# tm7_LEDs.net
KiCad netlist of a schematic drawn in EAGLE
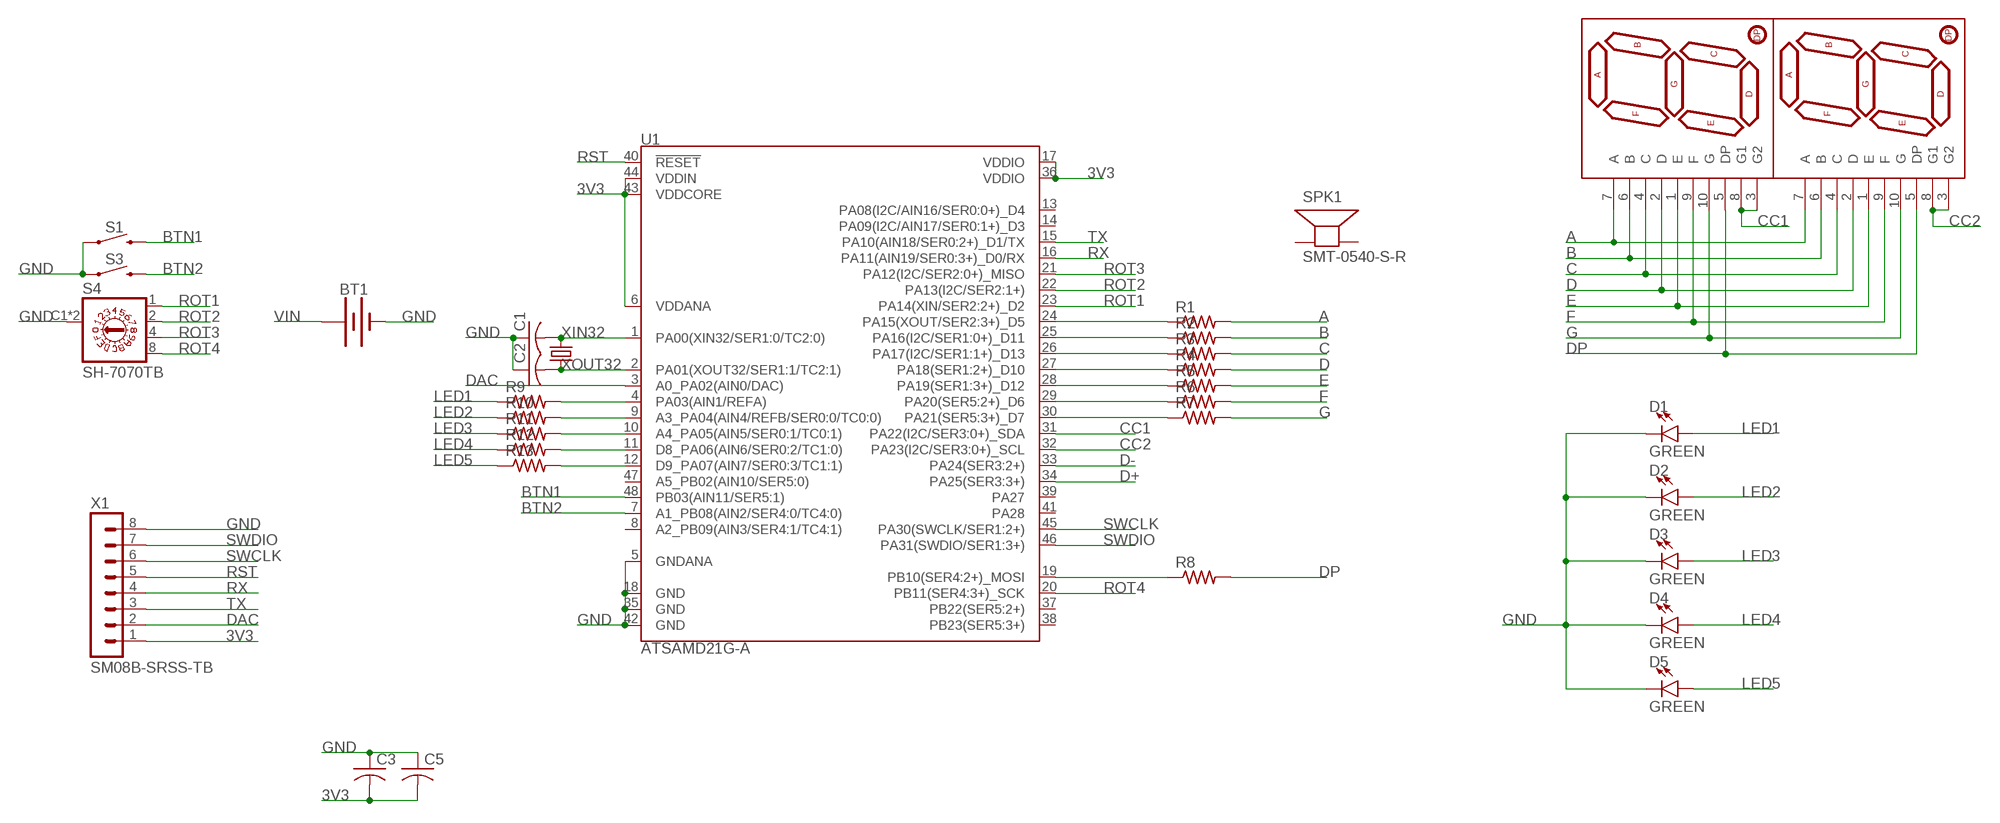
[diagram p0: schematic, sheet 1]

(export (version "E")
  (design (tool "Eeschema 10.0.6"))
  (components
    (comp (ref "BT1")
      (value "BATTERY-20MM_SMD_4LEGS_OVERPASTE_INNER")
      (footprint "eagle-import:BATTCON_20MM_4LEGS_OVERPASTE_INNER")
      (libsource (lib "eagle-import") (part "BATTERY-20MM_SMD_4LEGS_OVERPASTE_INNER"))
    )
    (comp (ref "C1")
      (value "C-USC0603")
      (footprint "eagle-import:C0603")
      (libsource (lib "eagle-import") (part "C-USC0603"))
    )
    (comp (ref "C2")
      (value "C-USC0603")
      (footprint "eagle-import:C0603")
      (libsource (lib "eagle-import") (part "C-USC0603"))
    )
    (comp (ref "C3")
      (value "C-USC0603")
      (footprint "eagle-import:C0603")
      (libsource (lib "eagle-import") (part "C-USC0603"))
    )
    (comp (ref "C5")
      (value "C-USC0603")
      (footprint "eagle-import:C0603")
      (libsource (lib "eagle-import") (part "C-USC0603"))
    )
    (comp (ref "D1")
      (value "GREEN")
      (footprint "eagle-import:LED-1206")
      (libsource (lib "eagle-import") (part "LED-GREEN1206"))
    )
    (comp (ref "D2")
      (value "GREEN")
      (footprint "eagle-import:LED-1206")
      (libsource (lib "eagle-import") (part "LED-GREEN1206"))
    )
    (comp (ref "D3")
      (value "GREEN")
      (footprint "eagle-import:LED-1206")
      (libsource (lib "eagle-import") (part "LED-GREEN1206"))
    )
    (comp (ref "D4")
      (value "GREEN")
      (footprint "eagle-import:LED-1206")
      (libsource (lib "eagle-import") (part "LED-GREEN1206"))
    )
    (comp (ref "D5")
      (value "GREEN")
      (footprint "eagle-import:LED-1206")
      (libsource (lib "eagle-import") (part "LED-GREEN1206"))
    )
    (comp (ref "R1")
      (value "R-US_R0603")
      (footprint "eagle-import:R0603")
      (libsource (lib "eagle-import") (part "R-US_R0603"))
    )
    (comp (ref "R2")
      (value "R-US_R0603")
      (footprint "eagle-import:R0603")
      (libsource (lib "eagle-import") (part "R-US_R0603"))
    )
    (comp (ref "R3")
      (value "R-US_R0603")
      (footprint "eagle-import:R0603")
      (libsource (lib "eagle-import") (part "R-US_R0603"))
    )
    (comp (ref "R4")
      (value "R-US_R0603")
      (footprint "eagle-import:R0603")
      (libsource (lib "eagle-import") (part "R-US_R0603"))
    )
    (comp (ref "R5")
      (value "R-US_R0603")
      (footprint "eagle-import:R0603")
      (libsource (lib "eagle-import") (part "R-US_R0603"))
    )
    (comp (ref "R6")
      (value "R-US_R0603")
      (footprint "eagle-import:R0603")
      (libsource (lib "eagle-import") (part "R-US_R0603"))
    )
    (comp (ref "R7")
      (value "R-US_R0603")
      (footprint "eagle-import:R0603")
      (libsource (lib "eagle-import") (part "R-US_R0603"))
    )
    (comp (ref "R8")
      (value "R-US_R0603")
      (footprint "eagle-import:R0603")
      (libsource (lib "eagle-import") (part "R-US_R0603"))
    )
    (comp (ref "R9")
      (value "R-US_R0603")
      (footprint "eagle-import:R0603")
      (libsource (lib "eagle-import") (part "R-US_R0603"))
    )
    (comp (ref "R10")
      (value "R-US_R0603")
      (footprint "eagle-import:R0603")
      (libsource (lib "eagle-import") (part "R-US_R0603"))
    )
    (comp (ref "R11")
      (value "R-US_R0603")
      (footprint "eagle-import:R0603")
      (libsource (lib "eagle-import") (part "R-US_R0603"))
    )
    (comp (ref "R12")
      (value "R-US_R0603")
      (footprint "eagle-import:R0603")
      (libsource (lib "eagle-import") (part "R-US_R0603"))
    )
    (comp (ref "R13")
      (value "R-US_R0603")
      (footprint "eagle-import:R0603")
      (libsource (lib "eagle-import") (part "R-US_R0603"))
    )
    (comp (ref "S1")
      (value "MOMENTARY-SWITCH-SPST-SMD-6.2MM-TALL")
      (footprint "eagle-import:TACTILE_SWITCH_SMD_6.2MM_TALL")
      (libsource (lib "eagle-import") (part "MOMENTARY-SWITCH-SPST-SMD-6.2MM-TALL"))
    )
    (comp (ref "S3")
      (value "MOMENTARY-SWITCH-SPST-SMD-6.2MM-TALL")
      (footprint "eagle-import:TACTILE_SWITCH_SMD_6.2MM_TALL")
      (libsource (lib "eagle-import") (part "MOMENTARY-SWITCH-SPST-SMD-6.2MM-TALL"))
    )
    (comp (ref "S4")
      (value "SH-7070TB")
      (footprint "eagle-import:SH-7070B")
      (fields (field (name "MF") "Nidec Copal"))
      (libsource (lib "eagle-import") (part "SH-7070TB"))
    )
    (comp (ref "SPK1")
      (value "SMT-0540-S-R")
      (footprint "eagle-import:SMT-0540-S-R")
      (fields (field (name "MF") "PUI"))
      (libsource (lib "eagle-import") (part "SMT-0540-S-R"))
    )
    (comp (ref "U$2")
      (value "7-SEGMENT-DISPLAY-1\"-RED")
      (footprint "eagle-import:7-SEGMENT-SMD")
      (libsource (lib "eagle-import") (part "7-SEGMENT-DISPLAY-1{dblquote}-RED"))
    )
    (comp (ref "U$3")
      (value "7-SEGMENT-DISPLAY-1\"-RED")
      (footprint "eagle-import:7-SEGMENT-SMD")
      (libsource (lib "eagle-import") (part "7-SEGMENT-DISPLAY-1{dblquote}-RED"))
    )
    (comp (ref "U1")
      (value "ATSAMD21G-A")
      (footprint "eagle-import:TQFP-48")
      (libsource (lib "eagle-import") (part "ATSAMD21G-A"))
    )
    (comp (ref "X1")
      (value "SM08B-SRSS-TB")
      (footprint "eagle-import:SM08B-SRSS-TB")
      (libsource (lib "eagle-import") (part "SM08B-SRSS-TB"))
    )
    (comp (ref "Y1")
      (value "32.768kHz")
      (footprint "eagle-import:CRYSTAL-SMD-3.2X1.5MM")
      (libsource (lib "eagle-import") (part "CRYSTAL-32.768KHZSMD-3.2X1.5"))
    )
  )
  (nets
    (net (code "1") (name "/3V3") (class "Default")
      (node (ref "C3") (pin "2") (pinfunction "2_2") (pintype "passive"))
      (node (ref "C5") (pin "2") (pinfunction "2_2") (pintype "passive"))
      (node (ref "U1") (pin "17") (pinfunction "VDDIO_17") (pintype "bidirectional"))
      (node (ref "U1") (pin "36") (pinfunction "VDDIO_36") (pintype "bidirectional"))
      (node (ref "U1") (pin "43") (pinfunction "VDDCORE_43") (pintype "bidirectional"))
      (node (ref "U1") (pin "44") (pinfunction "VDDIN_44") (pintype "bidirectional"))
      (node (ref "U1") (pin "6") (pinfunction "VDDANA_6") (pintype "bidirectional"))
      (node (ref "X1") (pin "1") (pinfunction "1_1") (pintype "passive"))
    )
    (net (code "2") (name "/A") (class "Default")
      (node (ref "R1") (pin "2") (pinfunction "2_2") (pintype "passive"))
      (node (ref "U$2") (pin "7") (pinfunction "A_7") (pintype "bidirectional"))
      (node (ref "U$3") (pin "7") (pinfunction "A_7") (pintype "bidirectional"))
    )
    (net (code "3") (name "/B") (class "Default")
      (node (ref "R2") (pin "2") (pinfunction "2_2") (pintype "passive"))
      (node (ref "U$2") (pin "6") (pinfunction "B_6") (pintype "bidirectional"))
      (node (ref "U$3") (pin "6") (pinfunction "B_6") (pintype "bidirectional"))
    )
    (net (code "4") (name "/BTN1") (class "Default")
      (node (ref "S1") (pin "B2") (pinfunction "2_B2") (pintype "passive"))
      (node (ref "U1") (pin "48") (pinfunction "PB03(AIN11/SER5:1)_48") (pintype "bidirectional"))
    )
    (net (code "5") (name "/BTN2") (class "Default")
      (node (ref "S3") (pin "B2") (pinfunction "2_B2") (pintype "passive"))
      (node (ref "U1") (pin "7") (pinfunction "A1_PB08(AIN2/SER4:0/TC4:0)_7") (pintype "bidirectional"))
    )
    (net (code "6") (name "/C") (class "Default")
      (node (ref "R3") (pin "2") (pinfunction "2_2") (pintype "passive"))
      (node (ref "U$2") (pin "4") (pinfunction "C_4") (pintype "bidirectional"))
      (node (ref "U$3") (pin "4") (pinfunction "C_4") (pintype "bidirectional"))
    )
    (net (code "7") (name "/CC1") (class "Default")
      (node (ref "U$2") (pin "3") (pinfunction "G2_3") (pintype "bidirectional"))
      (node (ref "U$2") (pin "8") (pinfunction "G1_8") (pintype "bidirectional"))
      (node (ref "U1") (pin "31") (pinfunction "PA22(I2C/SER3:0+)_SDA_31") (pintype "bidirectional"))
    )
    (net (code "8") (name "/CC2") (class "Default")
      (node (ref "U$3") (pin "3") (pinfunction "G2_3") (pintype "bidirectional"))
      (node (ref "U$3") (pin "8") (pinfunction "G1_8") (pintype "bidirectional"))
      (node (ref "U1") (pin "32") (pinfunction "PA23(I2C/SER3:0+)_SCL_32") (pintype "bidirectional"))
    )
    (net (code "9") (name "/D") (class "Default")
      (node (ref "R4") (pin "2") (pinfunction "2_2") (pintype "passive"))
      (node (ref "U$2") (pin "2") (pinfunction "D_2") (pintype "bidirectional"))
      (node (ref "U$3") (pin "2") (pinfunction "D_2") (pintype "bidirectional"))
    )
    (net (code "10") (name "/D+") (class "Default")
      (node (ref "U1") (pin "34") (pinfunction "PA25(SER3:3+)_34") (pintype "bidirectional"))
    )
    (net (code "11") (name "/D-") (class "Default")
      (node (ref "U1") (pin "33") (pinfunction "PA24(SER3:2+)_33") (pintype "bidirectional"))
    )
    (net (code "12") (name "/DAC") (class "Default")
      (node (ref "U1") (pin "3") (pinfunction "A0_PA02(AIN0/DAC)_3") (pintype "bidirectional"))
      (node (ref "X1") (pin "2") (pinfunction "2_2") (pintype "passive"))
    )
    (net (code "13") (name "/DP") (class "Default")
      (node (ref "R8") (pin "2") (pinfunction "2_2") (pintype "passive"))
      (node (ref "U$2") (pin "5") (pinfunction "DP_5") (pintype "bidirectional"))
      (node (ref "U$3") (pin "5") (pinfunction "DP_5") (pintype "bidirectional"))
    )
    (net (code "14") (name "/E") (class "Default")
      (node (ref "R5") (pin "2") (pinfunction "2_2") (pintype "passive"))
      (node (ref "U$2") (pin "1") (pinfunction "E_1") (pintype "bidirectional"))
      (node (ref "U$3") (pin "1") (pinfunction "E_1") (pintype "bidirectional"))
    )
    (net (code "15") (name "/F") (class "Default")
      (node (ref "R6") (pin "2") (pinfunction "2_2") (pintype "passive"))
      (node (ref "U$2") (pin "9") (pinfunction "F_9") (pintype "bidirectional"))
      (node (ref "U$3") (pin "9") (pinfunction "F_9") (pintype "bidirectional"))
    )
    (net (code "16") (name "/G") (class "Default")
      (node (ref "R7") (pin "2") (pinfunction "2_2") (pintype "passive"))
      (node (ref "U$2") (pin "10") (pinfunction "G_10") (pintype "bidirectional"))
      (node (ref "U$3") (pin "10") (pinfunction "G_10") (pintype "bidirectional"))
    )
    (net (code "17") (name "/GND") (class "Default")
      (node (ref "BT1") (pin "2") (pinfunction "-_2") (pintype "power_in"))
      (node (ref "C1") (pin "1") (pinfunction "1_1") (pintype "passive"))
      (node (ref "C2") (pin "1") (pinfunction "1_1") (pintype "passive"))
      (node (ref "C3") (pin "1") (pinfunction "1_1") (pintype "passive"))
      (node (ref "C5") (pin "1") (pinfunction "1_1") (pintype "passive"))
      (node (ref "D1") (pin "C") (pinfunction "C_C") (pintype "passive"))
      (node (ref "D2") (pin "C") (pinfunction "C_C") (pintype "passive"))
      (node (ref "D3") (pin "C") (pinfunction "C_C") (pintype "passive"))
      (node (ref "D4") (pin "C") (pinfunction "C_C") (pintype "passive"))
      (node (ref "D5") (pin "C") (pinfunction "C_C") (pintype "passive"))
      (node (ref "S1") (pin "A2") (pinfunction "1_A2") (pintype "passive"))
      (node (ref "S3") (pin "A2") (pinfunction "1_A2") (pintype "passive"))
      (node (ref "S4") (pin "C1") (pinfunction "C_C1") (pintype "passive"))
      (node (ref "S4") (pin "C2") (pinfunction "C_C2") (pintype "passive"))
      (node (ref "U1") (pin "18") (pinfunction "GND_18") (pintype "bidirectional"))
      (node (ref "U1") (pin "35") (pinfunction "GND_35") (pintype "bidirectional"))
      (node (ref "U1") (pin "42") (pinfunction "GND_42") (pintype "bidirectional"))
      (node (ref "U1") (pin "5") (pinfunction "GNDANA_5") (pintype "bidirectional"))
      (node (ref "X1") (pin "8") (pinfunction "8_8") (pintype "passive"))
    )
    (net (code "18") (name "/LED1") (class "Default")
      (node (ref "D1") (pin "A") (pinfunction "A_A") (pintype "passive"))
      (node (ref "R9") (pin "1") (pinfunction "1_1") (pintype "passive"))
    )
    (net (code "19") (name "/LED2") (class "Default")
      (node (ref "D2") (pin "A") (pinfunction "A_A") (pintype "passive"))
      (node (ref "R10") (pin "1") (pinfunction "1_1") (pintype "passive"))
    )
    (net (code "20") (name "/LED3") (class "Default")
      (node (ref "D3") (pin "A") (pinfunction "A_A") (pintype "passive"))
      (node (ref "R11") (pin "1") (pinfunction "1_1") (pintype "passive"))
    )
    (net (code "21") (name "/LED4") (class "Default")
      (node (ref "D4") (pin "A") (pinfunction "A_A") (pintype "passive"))
      (node (ref "R12") (pin "1") (pinfunction "1_1") (pintype "passive"))
    )
    (net (code "22") (name "/LED5") (class "Default")
      (node (ref "D5") (pin "A") (pinfunction "A_A") (pintype "passive"))
      (node (ref "R13") (pin "1") (pinfunction "1_1") (pintype "passive"))
    )
    (net (code "23") (name "/ROT1") (class "Default")
      (node (ref "S4") (pin "1") (pinfunction "1_1") (pintype "passive"))
      (node (ref "U1") (pin "23") (pinfunction "PA14(XIN/SER2:2+)_D2_23") (pintype "bidirectional"))
    )
    (net (code "24") (name "/ROT2") (class "Default")
      (node (ref "S4") (pin "2") (pinfunction "2_2") (pintype "passive"))
      (node (ref "U1") (pin "22") (pinfunction "PA13(I2C/SER2:1+)_22") (pintype "bidirectional"))
    )
    (net (code "25") (name "/ROT3") (class "Default")
      (node (ref "S4") (pin "4") (pinfunction "4_4") (pintype "passive"))
      (node (ref "U1") (pin "21") (pinfunction "PA12(I2C/SER2:0+)_MISO_21") (pintype "bidirectional"))
    )
    (net (code "26") (name "/ROT4") (class "Default")
      (node (ref "S4") (pin "8") (pinfunction "8_8") (pintype "passive"))
      (node (ref "U1") (pin "20") (pinfunction "PB11(SER4:3+)_SCK_20") (pintype "bidirectional"))
    )
    (net (code "27") (name "/RST") (class "Default")
      (node (ref "U1") (pin "40") (pinfunction "~{RESET}_40") (pintype "bidirectional"))
      (node (ref "X1") (pin "5") (pinfunction "5_5") (pintype "passive"))
    )
    (net (code "28") (name "/RX") (class "Default")
      (node (ref "U1") (pin "16") (pinfunction "PA11(AIN19/SER0:3+)_D0/RX_16") (pintype "bidirectional"))
      (node (ref "X1") (pin "4") (pinfunction "4_4") (pintype "passive"))
    )
    (net (code "29") (name "/SWCLK") (class "Default")
      (node (ref "U1") (pin "45") (pinfunction "PA30(SWCLK/SER1:2+)_45") (pintype "bidirectional"))
      (node (ref "X1") (pin "6") (pinfunction "6_6") (pintype "passive"))
    )
    (net (code "30") (name "/SWDIO") (class "Default")
      (node (ref "U1") (pin "46") (pinfunction "PA31(SWDIO/SER1:3+)_46") (pintype "bidirectional"))
      (node (ref "X1") (pin "7") (pinfunction "7_7") (pintype "passive"))
    )
    (net (code "31") (name "/TX") (class "Default")
      (node (ref "U1") (pin "15") (pinfunction "PA10(AIN18/SER0:2+)_D1/TX_15") (pintype "bidirectional"))
      (node (ref "X1") (pin "3") (pinfunction "3_3") (pintype "passive"))
    )
    (net (code "32") (name "/VIN") (class "Default")
      (node (ref "BT1") (pin "1") (pinfunction "+_1") (pintype "power_in"))
    )
    (net (code "33") (name "/XIN32") (class "Default")
      (node (ref "C1") (pin "2") (pinfunction "2_2") (pintype "passive"))
      (node (ref "U1") (pin "1") (pinfunction "PA00(XIN32/SER1:0/TC2:0)_1") (pintype "bidirectional"))
      (node (ref "Y1") (pin "P$2") (pinfunction "2_P$2") (pintype "passive"))
    )
    (net (code "34") (name "/XOUT32") (class "Default")
      (node (ref "C2") (pin "2") (pinfunction "2_2") (pintype "passive"))
      (node (ref "U1") (pin "2") (pinfunction "PA01(XOUT32/SER1:1/TC2:1)_2") (pintype "bidirectional"))
      (node (ref "Y1") (pin "P$1") (pinfunction "1_P$1") (pintype "passive"))
    )
    (net (code "35") (name "Net-(U1-A3_PA04(AIN4{slash}REFB{slash}SER0:0{slash}TC0:0))") (class "Default")
      (node (ref "R10") (pin "2") (pinfunction "2_2") (pintype "passive"))
      (node (ref "U1") (pin "9") (pinfunction "A3_PA04(AIN4/REFB/SER0:0/TC0:0)_9") (pintype "bidirectional"))
    )
    (net (code "36") (name "Net-(U1-A4_PA05(AIN5{slash}SER0:1{slash}TC0:1))") (class "Default")
      (node (ref "R11") (pin "2") (pinfunction "2_2") (pintype "passive"))
      (node (ref "U1") (pin "10") (pinfunction "A4_PA05(AIN5/SER0:1/TC0:1)_10") (pintype "bidirectional"))
    )
    (net (code "37") (name "Net-(U1-D8_PA06(AIN6{slash}SER0:2{slash}TC1:0))") (class "Default")
      (node (ref "R12") (pin "2") (pinfunction "2_2") (pintype "passive"))
      (node (ref "U1") (pin "11") (pinfunction "D8_PA06(AIN6/SER0:2/TC1:0)_11") (pintype "bidirectional"))
    )
    (net (code "38") (name "Net-(U1-D9_PA07(AIN7{slash}SER0:3{slash}TC1:1))") (class "Default")
      (node (ref "R13") (pin "2") (pinfunction "2_2") (pintype "passive"))
      (node (ref "U1") (pin "12") (pinfunction "D9_PA07(AIN7/SER0:3/TC1:1)_12") (pintype "bidirectional"))
    )
    (net (code "39") (name "Net-(U1-PA03(AIN1{slash}REFA))") (class "Default")
      (node (ref "R9") (pin "2") (pinfunction "2_2") (pintype "passive"))
      (node (ref "U1") (pin "4") (pinfunction "PA03(AIN1/REFA)_4") (pintype "bidirectional"))
    )
    (net (code "40") (name "Net-(U1-PA15(XOUT{slash}SER2:3+)_D5)") (class "Default")
      (node (ref "R1") (pin "1") (pinfunction "1_1") (pintype "passive"))
      (node (ref "U1") (pin "24") (pinfunction "PA15(XOUT/SER2:3+)_D5_24") (pintype "bidirectional"))
    )
    (net (code "41") (name "Net-(U1-PA16(I2C{slash}SER1:0+)_D11)") (class "Default")
      (node (ref "R2") (pin "1") (pinfunction "1_1") (pintype "passive"))
      (node (ref "U1") (pin "25") (pinfunction "PA16(I2C/SER1:0+)_D11_25") (pintype "bidirectional"))
    )
    (net (code "42") (name "Net-(U1-PA17(I2C{slash}SER1:1+)_D13)") (class "Default")
      (node (ref "R3") (pin "1") (pinfunction "1_1") (pintype "passive"))
      (node (ref "U1") (pin "26") (pinfunction "PA17(I2C/SER1:1+)_D13_26") (pintype "bidirectional"))
    )
    (net (code "43") (name "Net-(U1-PA18(SER1:2+)_D10)") (class "Default")
      (node (ref "R4") (pin "1") (pinfunction "1_1") (pintype "passive"))
      (node (ref "U1") (pin "27") (pinfunction "PA18(SER1:2+)_D10_27") (pintype "bidirectional"))
    )
    (net (code "44") (name "Net-(U1-PA19(SER1:3+)_D12)") (class "Default")
      (node (ref "R5") (pin "1") (pinfunction "1_1") (pintype "passive"))
      (node (ref "U1") (pin "28") (pinfunction "PA19(SER1:3+)_D12_28") (pintype "bidirectional"))
    )
    (net (code "45") (name "Net-(U1-PA20(SER5:2+)_D6)") (class "Default")
      (node (ref "R6") (pin "1") (pinfunction "1_1") (pintype "passive"))
      (node (ref "U1") (pin "29") (pinfunction "PA20(SER5:2+)_D6_29") (pintype "bidirectional"))
    )
    (net (code "46") (name "Net-(U1-PA21(SER5:3+)_D7)") (class "Default")
      (node (ref "R7") (pin "1") (pinfunction "1_1") (pintype "passive"))
      (node (ref "U1") (pin "30") (pinfunction "PA21(SER5:3+)_D7_30") (pintype "bidirectional"))
    )
    (net (code "47") (name "Net-(U1-PB10(SER4:2+)_MOSI)") (class "Default")
      (node (ref "R8") (pin "1") (pinfunction "1_1") (pintype "passive"))
      (node (ref "U1") (pin "19") (pinfunction "PB10(SER4:2+)_MOSI_19") (pintype "bidirectional"))
    )
    (net (code "48") (name "unconnected-(SPK1-+-Pad-)") (class "Default")
      (node (ref "SPK1") (pin "-") (pinfunction "+_-") (pintype "passive"))
    )
    (net (code "49") (name "unconnected-(SPK1---Pad+)") (class "Default")
      (node (ref "SPK1") (pin "+") (pinfunction "-_+") (pintype "passive"))
    )
    (net (code "50") (name "unconnected-(U1-A2_PB09(AIN3{slash}SER4:1{slash}TC4:1)-Pad8)") (class "Default")
      (node (ref "U1") (pin "8") (pinfunction "A2_PB09(AIN3/SER4:1/TC4:1)_8") (pintype "bidirectional"))
    )
    (net (code "51") (name "unconnected-(U1-A5_PB02(AIN10{slash}SER5:0)-Pad47)") (class "Default")
      (node (ref "U1") (pin "47") (pinfunction "A5_PB02(AIN10/SER5:0)_47") (pintype "bidirectional"))
    )
    (net (code "52") (name "unconnected-(U1-PA08(I2C{slash}AIN16{slash}SER0:0+)_D4-Pad13)") (class "Default")
      (node (ref "U1") (pin "13") (pinfunction "PA08(I2C/AIN16/SER0:0+)_D4_13") (pintype "bidirectional"))
    )
    (net (code "53") (name "unconnected-(U1-PA09(I2C{slash}AIN17{slash}SER0:1+)_D3-Pad14)") (class "Default")
      (node (ref "U1") (pin "14") (pinfunction "PA09(I2C/AIN17/SER0:1+)_D3_14") (pintype "bidirectional"))
    )
    (net (code "54") (name "unconnected-(U1-PA27-Pad39)") (class "Default")
      (node (ref "U1") (pin "39") (pinfunction "PA27_39") (pintype "bidirectional"))
    )
    (net (code "55") (name "unconnected-(U1-PA28-Pad41)") (class "Default")
      (node (ref "U1") (pin "41") (pinfunction "PA28_41") (pintype "bidirectional"))
    )
    (net (code "56") (name "unconnected-(U1-PB22(SER5:2+)-Pad37)") (class "Default")
      (node (ref "U1") (pin "37") (pinfunction "PB22(SER5:2+)_37") (pintype "bidirectional"))
    )
    (net (code "57") (name "unconnected-(U1-PB23(SER5:3+)-Pad38)") (class "Default")
      (node (ref "U1") (pin "38") (pinfunction "PB23(SER5:3+)_38") (pintype "bidirectional"))
    )
  )
)
